# ProPrj_TC264_2025-12_27_1.net
KiCad netlist of a schematic drawn in EasyEDA Pro
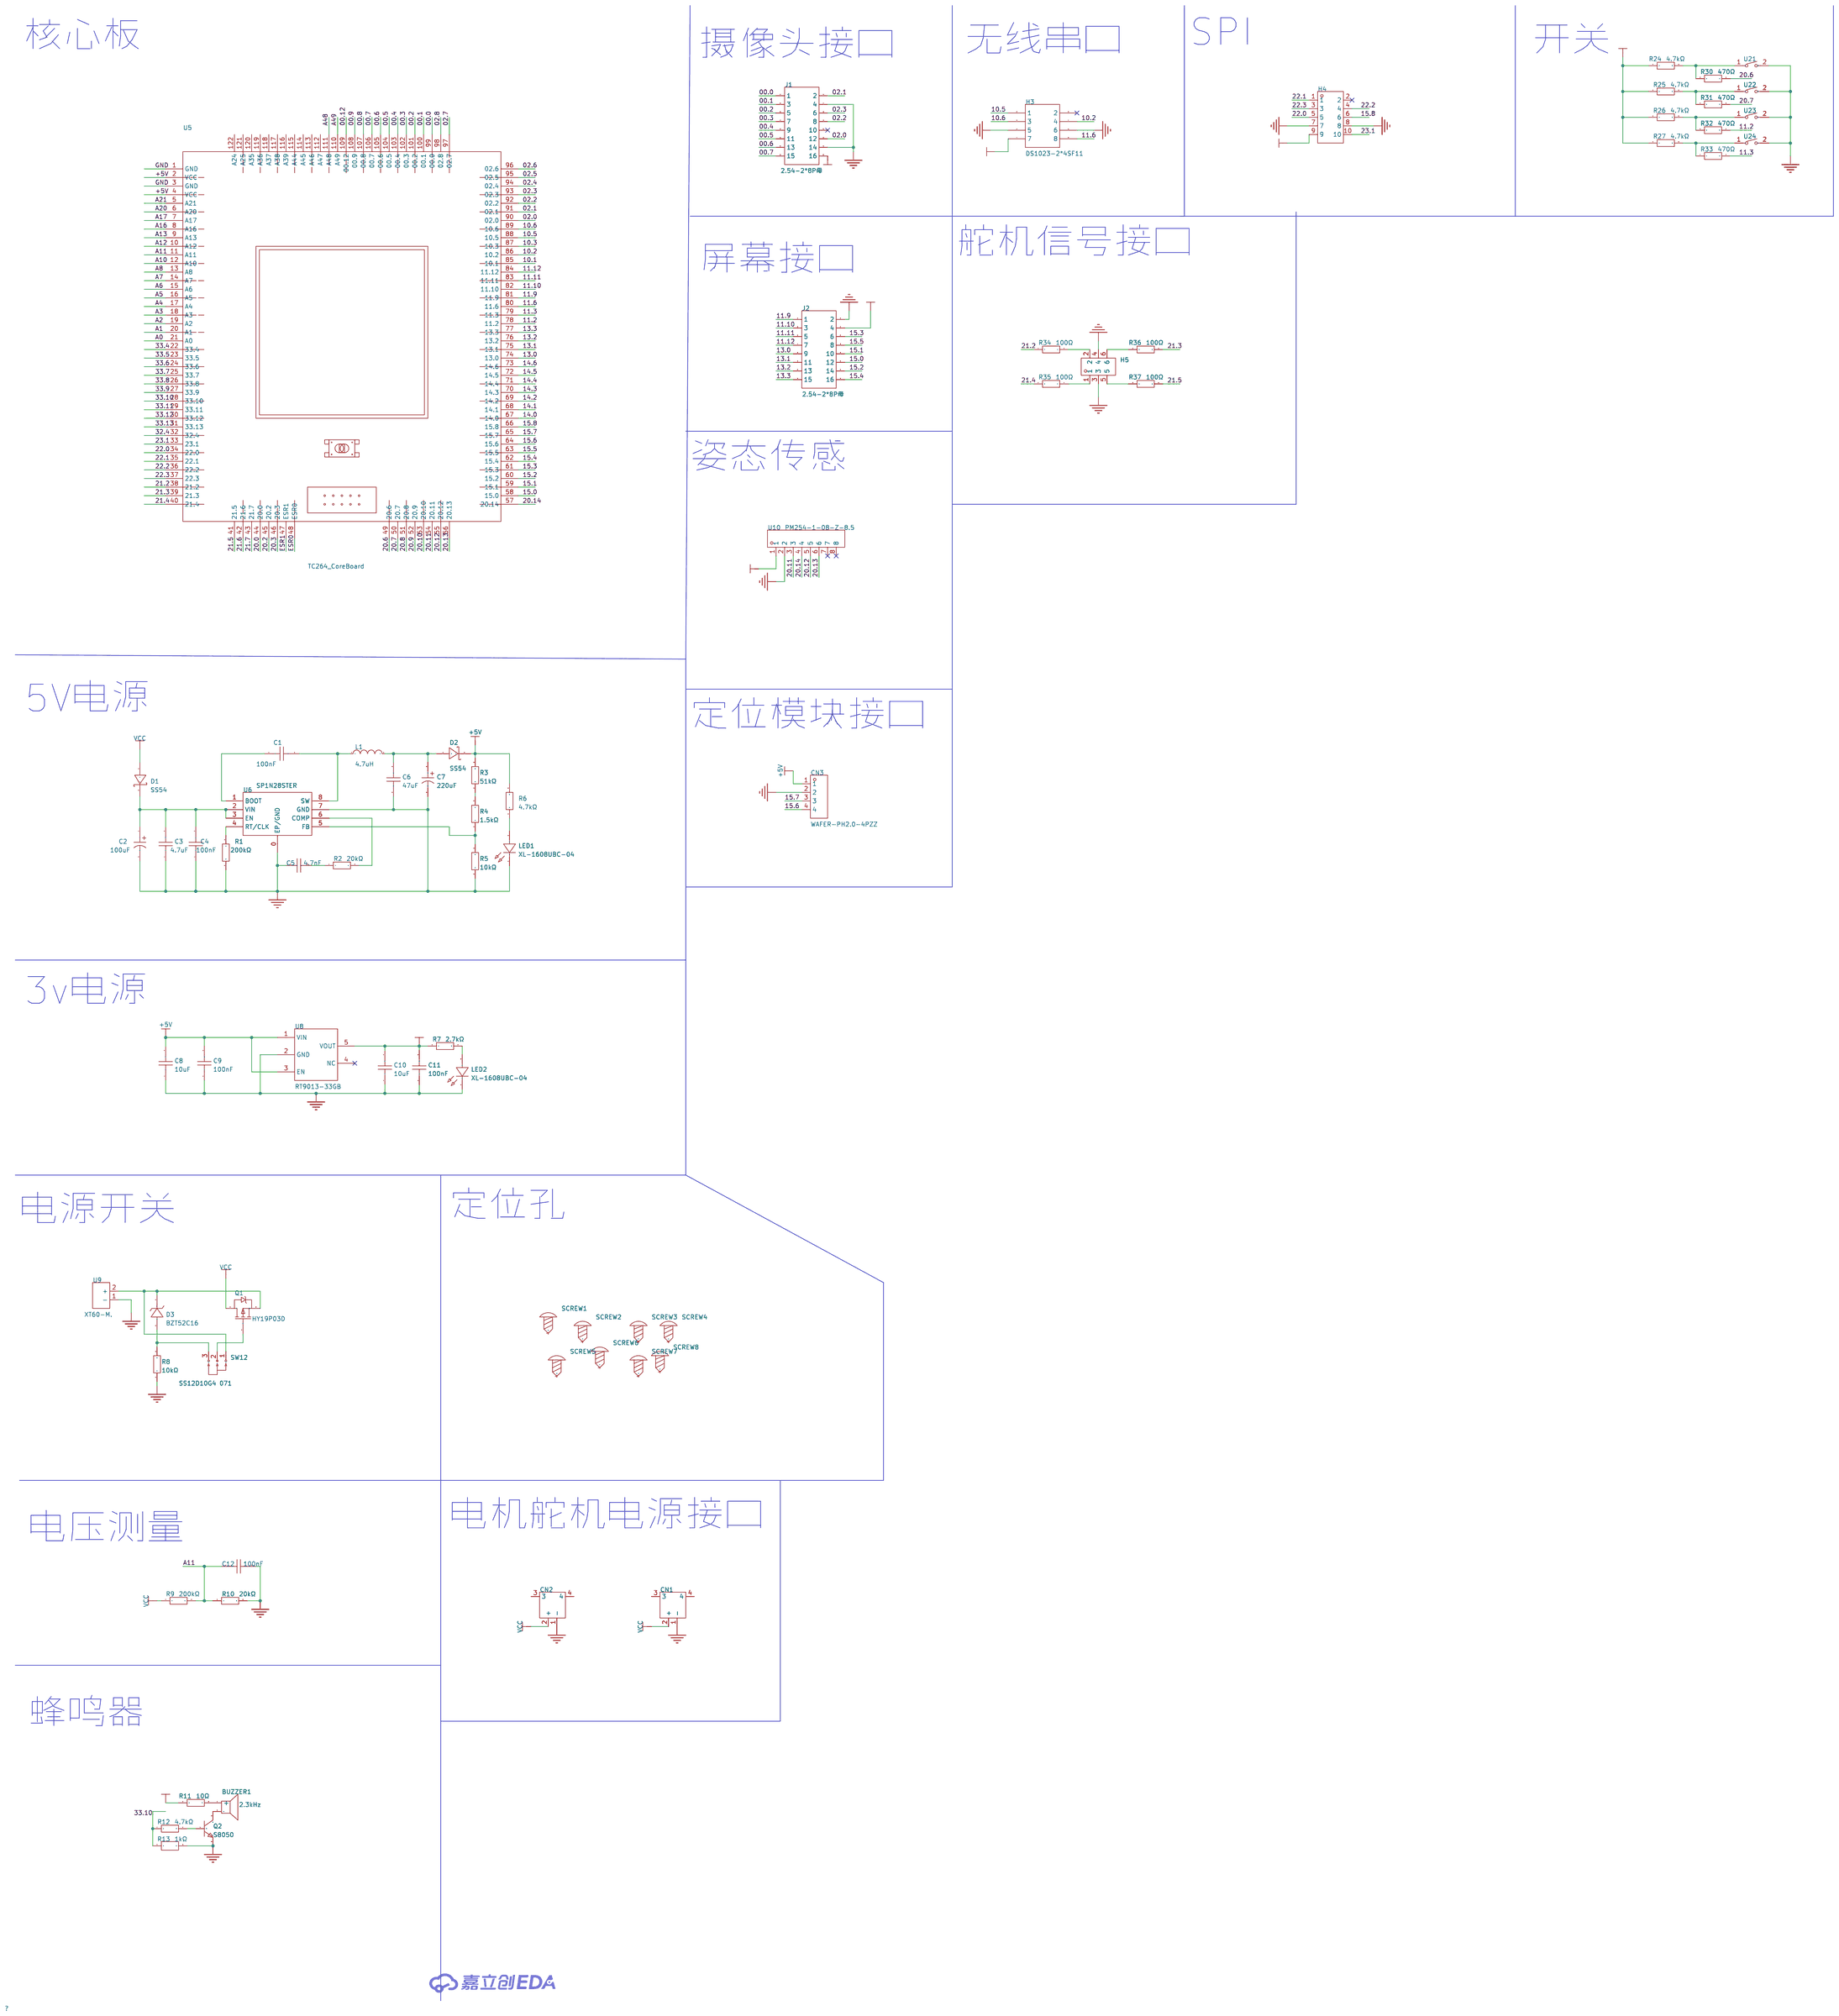
[diagram p0: schematic sheet]

(export (version "E")
  (design (tool "Eeschema 10.0.6"))
  (components
    (comp (ref "BUZZER1")
      (value "2.3kHz")
      (footprint "easyedapro:BUZ-TH_BD12.0-P7.60-D0.6-FD")
      (description "驱动方式:有源(内含驱动线路);构造类型:电磁式;频率:2.3kHz;声压(SPL):85dB;")
      (fields (field (name "Manufacturer Part") "TMB12A03") (field (name "Manufacturer") "华能"))
      (libsource (lib "easyedapro") (part "TMB12A03"))
    )
    (comp (ref "C1")
      (value "100nF")
      (footprint "easyedapro:C0603")
      (description "容值:100nF;精度:±10%;额定电压:50V;材质(温度系数):X7R;")
      (fields
        (field (name "Manufacturer Part") "CC0603KRX7R9BB104")
        (field (name "Manufacturer") "YAGEO(国巨)")
      )
      (libsource (lib "") (part "CC0603KRX7R9BB104_1"))
    )
    (comp (ref "C2")
      (value "100uF")
      (footprint "easyedapro:CAP-TH_BD6.3-P2.60-D0.6-FD-1")
      (description "容值:100uF;精度:±20%;额定电压:35V;纹波电流:2.6A@100kHz;等效串联电阻(ESR):28mΩ@100kHz;类型:聚合物;")
      (fields (field (name "Manufacturer Part") "JVJ25V100M6x5") (field (name "Manufacturer") "JIERR(捷而瑞)"))
      (libsource (lib "easyedapro") (part "PA35V100M6X8"))
    )
    (comp (ref "C3")
      (value "4.7uF")
      (footprint "easyedapro:C1206")
      (description "容值:4.7uF;精度:±10%;额定电压:35V;材质(温度系数):X5R;")
      (fields
        (field (name "Manufacturer Part") "CGA1206X5R475K350NT")
        (field (name "Manufacturer") "HRE(芯声)")
      )
      (libsource (lib "easyedapro") (part "CGA1206X5R475K350NT"))
    )
    (comp (ref "C4")
      (value "100nF")
      (footprint "easyedapro:C0603")
      (description "容值:100nF;精度:±10%;额定电压:50V;温度系数:X7R;")
      (fields
        (field (name "Manufacturer Part") "CC0603KRX7R9BB104")
        (field (name "Manufacturer") "YAGEO(国巨)")
      )
      (libsource (lib "easyedapro") (part "CC0603KRX7R9BB104"))
    )
    (comp (ref "C5")
      (value "4.7nF")
      (footprint "easyedapro:C0603")
      (description "容值:4.7nF;精度:±10%;额定电压:50V;温度系数:X7R;")
      (fields
        (field (name "Manufacturer Part") "CL10B472KB8NNNC")
        (field (name "Manufacturer") "SAMSUNG(三星)")
      )
      (libsource (lib "easyedapro") (part "CL10B472KB8NNNC"))
    )
    (comp (ref "C6")
      (value "47uF")
      (footprint "easyedapro:C1206")
      (description "容值:47uF;精度:±20%;额定电压:25V;温度系数:X5R;")
      (fields
        (field (name "Manufacturer Part") "HGC1206R5476M250NSPJ")
        (field (name "Manufacturer") "Chinocera(华瓷)")
      )
      (libsource (lib "easyedapro") (part "HGC1206R5476M250NSPJ"))
    )
    (comp (ref "C7")
      (value "220uF")
      (footprint "easyedapro:CAP-TH_BD10.0-P5.00-D0.6-FD_2")
      (description "容值:220uF;精度:±20%;额定电压:50V;纹波电流:3.5A@100kHz;等效串联电阻(ESR):20mΩ@100kHz;类型:聚合物;")
      (fields (field (name "Manufacturer Part") "RVT25V220M6X8") (field (name "Manufacturer") "JIERR(捷而瑞)"))
      (libsource (lib "easyedapro") (part "PA50V220M10X12"))
    )
    (comp (ref "C8")
      (value "10uF")
      (footprint "easyedapro:C0603")
      (description "容值:10uF;精度:±20%;额定电压:25V;温度系数:X5R;")
      (fields
        (field (name "Manufacturer Part") "CL10A106MA8NRNC")
        (field (name "Manufacturer") "SAMSUNG(三星)")
      )
      (libsource (lib "easyedapro") (part "CL10A106MA8NRNC"))
    )
    (comp (ref "C9")
      (value "100nF")
      (footprint "easyedapro:C0603")
      (description "容值:100nF;精度:±10%;额定电压:50V;温度系数:X7R;")
      (fields
        (field (name "Manufacturer Part") "CGA0603X7R104K500JT")
        (field (name "Manufacturer") "HRE(芯声)")
      )
      (libsource (lib "easyedapro") (part "CGA0603X7R104K500JT"))
    )
    (comp (ref "C10")
      (value "10uF")
      (footprint "easyedapro:C0603")
      (description "容值:10uF;精度:±20%;额定电压:25V;温度系数:X5R;")
      (fields
        (field (name "Manufacturer Part") "CL10A106MA8NRNC")
        (field (name "Manufacturer") "SAMSUNG(三星)")
      )
      (libsource (lib "easyedapro") (part "CL10A106MA8NRNC"))
    )
    (comp (ref "C11")
      (value "100nF")
      (footprint "easyedapro:C0603")
      (description "容值:100nF;精度:±10%;额定电压:50V;温度系数:X7R;")
      (fields
        (field (name "Manufacturer Part") "CGA0603X7R104K500JT")
        (field (name "Manufacturer") "HRE(芯声)")
      )
      (libsource (lib "easyedapro") (part "CGA0603X7R104K500JT"))
    )
    (comp (ref "C12")
      (value "100nF")
      (footprint "easyedapro:C0603")
      (description "容值:100nF;精度:±10%;额定电压:50V;温度系数:X7R;")
      (fields
        (field (name "Manufacturer Part") "FCC0603B104K500CT")
        (field (name "Manufacturer") "FOJAN(富捷)")
      )
      (libsource (lib "easyedapro") (part "FCC0603B104K500CT"))
    )
    (comp (ref "CN1")
      (value "XT30PW-M30.G.Y")
      (footprint "easyedapro:CONN-TH_XT30PW-M")
      (description "类别:-;类型1:-;")
      (fields (field (name "Manufacturer") "AMASS(艾迈斯)"))
      (libsource (lib "easyedapro") (part "XT30PW-M"))
    )
    (comp (ref "CN2")
      (value "XT30PW-M30.G.Y")
      (footprint "easyedapro:CONN-TH_XT30PW-M")
      (description "类别:-;类型1:-;")
      (fields (field (name "Manufacturer") "AMASS(艾迈斯)"))
      (libsource (lib "easyedapro") (part "XT30PW-M"))
    )
    (comp (ref "CN3")
      (value "WAFER-PH2.0-4PZZ")
      (footprint "easyedapro:CONN-TH_4P-P2.00_FWF20001-S04S22W5B")
      (fields (field (name "Manufacturer") "XUNPU(讯普)"))
      (libsource (lib "easyedapro") (part "WAFER-PH2.0-4PZZ"))
    )
    (comp (ref "D1")
      (value "SS54")
      (footprint "easyedapro:footprint_93fc")
      (fields (field (name "Manufacturer") "MDD"))
      (libsource (lib "easyedapro") (part "SS54"))
    )
    (comp (ref "D2")
      (value "SS54")
      (footprint "easyedapro:SMA_L4.4-W2.8-LS5.4-R-RD")
      (description "二极管配置:独立式;正向压降(Vf):550mV@5A;直流反向耐压(Vr):40V;整流电流:5A;")
      (fields (field (name "Manufacturer") "MDD(辰达半导体)"))
      (libsource (lib "easyedapro") (part "SS54_C22452"))
    )
    (comp (ref "D3")
      (value "BZT52C16")
      (footprint "easyedapro:SOD-123_L2.7-W1.7-LS3.8-RD")
      (description "二极管配置:独立式;稳压值(标称值):16V;稳压值(范围):15.3V~17.1V;耗散功率(Pd):500mW;")
      (fields (field (name "Manufacturer") "TWGMC(迪嘉)"))
      (libsource (lib "easyedapro") (part "BZT52C16_C727007"))
    )
    (comp (ref "H3")
      (value "DS1023-2*4SF11")
      (footprint "easyedapro:HDR-TH_8P-P2.54-V-F-R2-C4-S2.54")
      (description "插孔结构:2x4P;间距:2.54mm;行距:2.54mm;安装方式:直插;排数:双排;总孔位数:8P;塑高:-;触头材质:-;触头镀层:-;")
      (fields (field (name "Manufacturer") "CONNFLY"))
      (libsource (lib "easyedapro") (part "DS1023-2*4SF11"))
    )
    (comp (ref "H4")
      (value "PM254V-12-10P-H85")
      (footprint "easyedapro:HDR-TH_10P-P2.54-V-F-R2-C5-S2.54")
      (description "插孔结构:2x5P;间距:2.54mm;行距:2.54mm;安装方式:直插;排数:双排;总孔位数:10P;塑高:-;触头材质:黄铜;触头镀层:-;")
      (fields (field (name "Manufacturer") "XFCN(兴飞)"))
      (libsource (lib "easyedapro") (part "PM254V-12-10P-H85"))
    )
    (comp (ref "H5")
      (value "PZ254V-12-6P")
      (footprint "easyedapro:HDR-TH_6P-P2.54-V-M-R2-C3-S2.54")
      (fields (field (name "Manufacturer") "XFCN(兴飞)"))
      (libsource (lib "easyedapro") (part "PZ254V-12-6P"))
    )
    (comp (ref "J1")
      (value "2.54-2*8P母")
      (footprint "easyedapro:HDR-TH_16P-P2.54-V-F-R2-C8-S2.54")
      (description "插孔结构:2x8P;间距:2.54mm;行距:2.54mm;安装方式:直插;排数:双排;总孔位数:16P;塑高:-;触头材质:黄铜;触头镀层:-;")
      (fields (field (name "Manufacturer") "BOOMELE(博穆精密)"))
      (libsource (lib "easyedapro") (part "Header-Female-2.54_2x8"))
    )
    (comp (ref "J2")
      (value "2.54-2*8P母")
      (footprint "easyedapro:HDR-TH_16P-P2.54-V-F-R2-C8-S2.54")
      (description "插孔结构:2x8P;间距:2.54mm;行距:2.54mm;安装方式:直插;排数:双排;总孔位数:16P;塑高:-;触头材质:黄铜;触头镀层:-;")
      (fields (field (name "Manufacturer") "BOOMELE(博穆精密)"))
      (libsource (lib "easyedapro") (part "Header-Female-2.54_2x8"))
    )
    (comp (ref "L1")
      (value "4.7uH")
      (footprint "easyedapro:IND-SMD_L5.4-W5.2_FXL0530")
      (description "电感值:4.7uH;精度:±20%;额定电流:4.5A;饱和电流(Isat):5A;类型:一体成型电感;")
      (fields (field (name "Manufacturer Part") "FXL0530-4R7-M") (field (name "Manufacturer") "cjiang(长江微电)"))
      (libsource (lib "easyedapro") (part "FXL0530-4R7-M"))
    )
    (comp (ref "LED1")
      (value "XL-1608UBC-04")
      (footprint "easyedapro:LED0603-RD_BLUE")
      (fields (field (name "Manufacturer") "XINGLIGHT(成兴光)"))
      (libsource (lib "easyedapro") (part "XL-1608UBC-04"))
    )
    (comp (ref "LED2")
      (value "XL-1608UBC-04")
      (footprint "easyedapro:LED0603-RD_BLUE")
      (fields (field (name "Manufacturer") "XINGLIGHT(成兴光)"))
      (libsource (lib "easyedapro") (part "XL-1608UBC-04"))
    )
    (comp (ref "Q1")
      (value "HY19P03D")
      (footprint "easyedapro:TO-252-2_L6.6-W6.1-P4.57-LS9.9-TL-CW")
      (fields (field (name "Manufacturer") "HUAYI(华羿微)"))
      (libsource (lib "easyedapro") (part "HY19P03D"))
    )
    (comp (ref "Q2")
      (value "S8050")
      (footprint "easyedapro:SOT-23-3_L3.0-W1.7-P0.95-LS2.9-BR")
      (description "晶体管类型:NPN;集电极电流(Ic):500mA;集射极击穿电压(Vceo):25V;耗散功率(Pd):300mW;直流电流增益(hFE):-;")
      (fields (field (name "Manufacturer") "MDD(辰达半导体)"))
      (libsource (lib "easyedapro") (part "S8050-J3Y"))
    )
    (comp (ref "R1")
      (value "200kΩ")
      (footprint "easyedapro:R0805")
      (description "电阻类型:厚膜电阻;阻值:200kΩ;精度:±1%;功率:125mW;最大工作电压:150V;温度系数:±100ppm/°C;")
      (fields
        (field (name "Manufacturer Part") "0805W8F2003T5E")
        (field (name "Manufacturer") "UNI-ROYAL(厚声)")
      )
      (libsource (lib "easyedapro") (part "0805W8F2003T5E"))
    )
    (comp (ref "R2")
      (value "20kΩ")
      (footprint "easyedapro:R0805")
      (description "电阻类型:厚膜电阻;阻值:20kΩ;精度:±1%;功率:125mW;最大工作电压:150V;温度系数:±100ppm/°C;")
      (fields
        (field (name "Manufacturer Part") "0805W8F2002T5E")
        (field (name "Manufacturer") "UNI-ROYAL(厚声)")
      )
      (libsource (lib "easyedapro") (part "0805W8F2002T5E"))
    )
    (comp (ref "R3")
      (value "51kΩ")
      (footprint "easyedapro:R0805")
      (description "电阻类型:厚膜电阻;阻值:51kΩ;精度:±1%;功率:125mW;工作电压:150V;温度系数:±100ppm/°C;")
      (fields
        (field (name "Manufacturer Part") "0805W8F5102T5E")
        (field (name "Manufacturer") "UNI-ROYAL(厚声)")
      )
      (libsource (lib "easyedapro") (part "0805W8F5102T5E"))
    )
    (comp (ref "R4")
      (value "1.5kΩ")
      (footprint "easyedapro:R0805")
      (description "电阻类型:厚膜电阻;阻值:1.5kΩ;精度:±1%;功率:125mW;最大工作电压:150V;温度系数:±100ppm/°C;")
      (fields
        (field (name "Manufacturer Part") "0805W8F1501T5E")
        (field (name "Manufacturer") "UNI-ROYAL(厚声)")
      )
      (libsource (lib "easyedapro") (part "0805W8F1501T5E"))
    )
    (comp (ref "R5")
      (value "10kΩ")
      (footprint "easyedapro:R0805")
      (description "电阻类型:厚膜电阻;阻值:10kΩ;精度:±5%;功率:125mW;工作电压:150V;温度系数:±100ppm/°C;")
      (fields
        (field (name "Manufacturer Part") "0805W8J0103T5E")
        (field (name "Manufacturer") "UNI-ROYAL(厚声)")
      )
      (libsource (lib "easyedapro") (part "0805W8J0103T5E"))
    )
    (comp (ref "R6")
      (value "4.7kΩ")
      (footprint "easyedapro:R0805")
      (description "电阻类型:厚膜电阻;阻值:4.7kΩ;精度:±1%;功率:125mW;最大工作电压:150V;温度系数:±100ppm/°C;")
      (fields
        (field (name "Manufacturer Part") "0805W8F4701T5E")
        (field (name "Manufacturer") "UNI-ROYAL(厚声)")
      )
      (libsource (lib "easyedapro") (part "0805W8F4701T5E"))
    )
    (comp (ref "R7")
      (value "2.7kΩ")
      (footprint "easyedapro:R0805")
      (description "电阻类型:厚膜电阻;阻值:2.7kΩ;精度:±1%;功率:125mW;工作电压:150V;温度系数:±100ppm/°C;")
      (fields
        (field (name "Manufacturer Part") "0805W8F2701T5E")
        (field (name "Manufacturer") "UNI-ROYAL(厚声)")
      )
      (libsource (lib "easyedapro") (part "0805W8F2701T5E"))
    )
    (comp (ref "R8")
      (value "10kΩ")
      (footprint "easyedapro:R0805")
      (description "电阻类型:厚膜电阻;阻值:10kΩ;精度:±1%;功率:125mW;工作电压:150V;温度系数:±100ppm/°C;")
      (fields
        (field (name "Manufacturer Part") "0805W8F1002T5E")
        (field (name "Manufacturer") "UNI-ROYAL(厚声)")
      )
      (libsource (lib "easyedapro") (part "0805W8F1002T5E"))
    )
    (comp (ref "R9")
      (value "200kΩ")
      (footprint "easyedapro:R0603")
      (description "电阻类型:厚膜电阻;阻值:200kΩ;精度:±1%;功率:100mW;最大工作电压:75V;温度系数:±100ppm/°C;")
      (fields
        (field (name "Manufacturer Part") "0603WAF2003T5E")
        (field (name "Manufacturer") "UNI-ROYAL(厚声)")
      )
      (libsource (lib "easyedapro") (part "0603WAF2003T5E"))
    )
    (comp (ref "R10")
      (value "20kΩ")
      (footprint "easyedapro:R0603")
      (description "电阻类型:厚膜电阻;阻值:20kΩ;精度:±1%;功率:100mW;工作电压:75V;温度系数:±100ppm/°C;")
      (fields
        (field (name "Manufacturer Part") "0603WAF2002T5E")
        (field (name "Manufacturer") "UNI-ROYAL(厚声)")
      )
      (libsource (lib "easyedapro") (part "0603WAF2002T5E"))
    )
    (comp (ref "R11")
      (value "10Ω")
      (footprint "easyedapro:R0603")
      (description "电阻类型:厚膜电阻;阻值:10Ω;精度:±1%;功率:100mW;工作电压:75V;温度系数:±400ppm/°C;")
      (fields
        (field (name "Manufacturer Part") "0603WAF100JT5E")
        (field (name "Manufacturer") "UNI-ROYAL(厚声)")
      )
      (libsource (lib "easyedapro") (part "0603WAF100JT5E"))
    )
    (comp (ref "R12")
      (value "4.7kΩ")
      (footprint "easyedapro:R0603")
      (description "电阻类型:厚膜电阻;阻值:4.7kΩ;精度:±1%;功率:100mW;工作电压:75V;温度系数:±100ppm/°C;")
      (fields
        (field (name "Manufacturer Part") "0603WAF4701T5E")
        (field (name "Manufacturer") "UNI-ROYAL(厚声)")
      )
      (libsource (lib "easyedapro") (part "0603WAF4701T5E"))
    )
    (comp (ref "R13")
      (value "1kΩ")
      (footprint "easyedapro:R0603")
      (description "电阻类型:厚膜电阻;阻值:1kΩ;精度:±1%;功率:100mW;工作电压:75V;温度系数:±100ppm/°C;")
      (fields (field (name "Manufacturer Part") "FRC0603F1001TS") (field (name "Manufacturer") "FOJAN(富捷)"))
      (libsource (lib "easyedapro") (part "FRC0603F1001TS"))
    )
    (comp (ref "R24")
      (value "4.7kΩ")
      (footprint "easyedapro:R0603")
      (description "电阻类型:厚膜电阻;阻值:4.7kΩ;精度:±1%;功率:100mW;工作电压:75V;温度系数:±100ppm/°C;")
      (fields
        (field (name "Manufacturer Part") "0603WAF4701T5E")
        (field (name "Manufacturer") "UNI-ROYAL(厚声)")
      )
      (libsource (lib "easyedapro") (part "0603WAF4701T5E"))
    )
    (comp (ref "R25")
      (value "4.7kΩ")
      (footprint "easyedapro:R0603")
      (description "电阻类型:厚膜电阻;阻值:4.7kΩ;精度:±1%;功率:100mW;工作电压:75V;温度系数:±100ppm/°C;")
      (fields
        (field (name "Manufacturer Part") "0603WAF4701T5E")
        (field (name "Manufacturer") "UNI-ROYAL(厚声)")
      )
      (libsource (lib "easyedapro") (part "0603WAF4701T5E"))
    )
    (comp (ref "R26")
      (value "4.7kΩ")
      (footprint "easyedapro:R0603")
      (description "电阻类型:厚膜电阻;阻值:4.7kΩ;精度:±1%;功率:100mW;工作电压:75V;温度系数:±100ppm/°C;")
      (fields
        (field (name "Manufacturer Part") "0603WAF4701T5E")
        (field (name "Manufacturer") "UNI-ROYAL(厚声)")
      )
      (libsource (lib "easyedapro") (part "0603WAF4701T5E"))
    )
    (comp (ref "R27")
      (value "4.7kΩ")
      (footprint "easyedapro:R0603")
      (description "电阻类型:厚膜电阻;阻值:4.7kΩ;精度:±1%;功率:100mW;工作电压:75V;温度系数:±100ppm/°C;")
      (fields
        (field (name "Manufacturer Part") "0603WAF4701T5E")
        (field (name "Manufacturer") "UNI-ROYAL(厚声)")
      )
      (libsource (lib "easyedapro") (part "0603WAF4701T5E"))
    )
    (comp (ref "R30")
      (value "470Ω")
      (footprint "easyedapro:R0603")
      (description "电阻类型:厚膜电阻;阻值:470Ω;精度:±1%;功率:100mW;工作电压:75V;温度系数:±100ppm/°C;")
      (fields
        (field (name "Manufacturer Part") "0603WAF4700T5E")
        (field (name "Manufacturer") "UNI-ROYAL(厚声)")
      )
      (libsource (lib "easyedapro") (part "0603WAF4700T5E"))
    )
    (comp (ref "R31")
      (value "470Ω")
      (footprint "easyedapro:R0603")
      (description "电阻类型:厚膜电阻;阻值:470Ω;精度:±1%;功率:100mW;工作电压:75V;温度系数:±100ppm/°C;")
      (fields
        (field (name "Manufacturer Part") "0603WAF4700T5E")
        (field (name "Manufacturer") "UNI-ROYAL(厚声)")
      )
      (libsource (lib "easyedapro") (part "0603WAF4700T5E"))
    )
    (comp (ref "R32")
      (value "470Ω")
      (footprint "easyedapro:R0603")
      (description "电阻类型:厚膜电阻;阻值:470Ω;精度:±1%;功率:100mW;工作电压:75V;温度系数:±100ppm/°C;")
      (fields
        (field (name "Manufacturer Part") "0603WAF4700T5E")
        (field (name "Manufacturer") "UNI-ROYAL(厚声)")
      )
      (libsource (lib "easyedapro") (part "0603WAF4700T5E"))
    )
    (comp (ref "R33")
      (value "470Ω")
      (footprint "easyedapro:R0603")
      (description "电阻类型:厚膜电阻;阻值:470Ω;精度:±1%;功率:100mW;工作电压:75V;温度系数:±100ppm/°C;")
      (fields
        (field (name "Manufacturer Part") "0603WAF4700T5E")
        (field (name "Manufacturer") "UNI-ROYAL(厚声)")
      )
      (libsource (lib "easyedapro") (part "0603WAF4700T5E"))
    )
    (comp (ref "R34")
      (value "100Ω")
      (footprint "easyedapro:R0603")
      (description "电阻类型:厚膜电阻;阻值:100Ω;精度:±1%;功率:100mW;最大工作电压:75V;温度系数:±200ppm/°C;")
      (fields
        (field (name "Manufacturer Part") "0603WAF1000T5E")
        (field (name "Manufacturer") "UNI-ROYAL(厚声)")
      )
      (libsource (lib "easyedapro") (part "0603WAF1000T5E"))
    )
    (comp (ref "R35")
      (value "100Ω")
      (footprint "easyedapro:R0603")
      (description "电阻类型:厚膜电阻;阻值:100Ω;精度:±1%;功率:100mW;最大工作电压:75V;温度系数:±200ppm/°C;")
      (fields
        (field (name "Manufacturer Part") "0603WAF1000T5E")
        (field (name "Manufacturer") "UNI-ROYAL(厚声)")
      )
      (libsource (lib "easyedapro") (part "0603WAF1000T5E"))
    )
    (comp (ref "R36")
      (value "100Ω")
      (footprint "easyedapro:R0603")
      (description "电阻类型:厚膜电阻;阻值:100Ω;精度:±1%;功率:100mW;最大工作电压:75V;温度系数:±200ppm/°C;")
      (fields
        (field (name "Manufacturer Part") "0603WAF1000T5E")
        (field (name "Manufacturer") "UNI-ROYAL(厚声)")
      )
      (libsource (lib "easyedapro") (part "0603WAF1000T5E"))
    )
    (comp (ref "R37")
      (value "100Ω")
      (footprint "easyedapro:R0603")
      (description "电阻类型:厚膜电阻;阻值:100Ω;精度:±1%;功率:100mW;最大工作电压:75V;温度系数:±200ppm/°C;")
      (fields
        (field (name "Manufacturer Part") "0603WAF1000T5E")
        (field (name "Manufacturer") "UNI-ROYAL(厚声)")
      )
      (libsource (lib "easyedapro") (part "0603WAF1000T5E"))
    )
    (comp (ref "SCREW1")
      (value "~")
      (footprint "easyedapro:M3螺丝")
      (libsource (lib "easyedapro") (part "螺丝孔"))
    )
    (comp (ref "SCREW2")
      (value "~")
      (footprint "easyedapro:M3螺丝")
      (libsource (lib "easyedapro") (part "螺丝孔"))
    )
    (comp (ref "SCREW3")
      (value "~")
      (footprint "easyedapro:M3螺丝")
      (libsource (lib "easyedapro") (part "螺丝孔"))
    )
    (comp (ref "SCREW4")
      (value "~")
      (footprint "easyedapro:M3螺丝")
      (libsource (lib "easyedapro") (part "螺丝孔"))
    )
    (comp (ref "SCREW5")
      (value "~")
      (footprint "easyedapro:M3螺丝")
      (libsource (lib "easyedapro") (part "螺丝孔"))
    )
    (comp (ref "SCREW6")
      (value "~")
      (footprint "easyedapro:M3螺丝")
      (libsource (lib "easyedapro") (part "螺丝孔"))
    )
    (comp (ref "SCREW7")
      (value "~")
      (footprint "easyedapro:M3螺丝")
      (libsource (lib "easyedapro") (part "螺丝孔"))
    )
    (comp (ref "SCREW8")
      (value "~")
      (footprint "easyedapro:M3螺丝")
      (libsource (lib "easyedapro") (part "螺丝孔"))
    )
    (comp (ref "SW12")
      (value "SS12D10G4 071")
      (footprint "easyedapro:SW-TH_SHOU-HAN_SS12D10G4")
      (description "电路结构:单刀双掷;安装方式:立插;开关颜色:-;额定电流(DC):2A;额定电压(DC):125V;额定电流(AC):-;额定电压(AC):-;机械寿命:3千次;")
      (fields (field (name "Manufacturer") "SHOU HAN(首韩)"))
      (libsource (lib "easyedapro") (part "SS12D10G4 071"))
    )
    (comp (ref "U5")
      (value "TC264_CoreBoard")
      (footprint "easyedapro:TC264_main")
      (libsource (lib "easyedapro") (part "TC264"))
    )
    (comp (ref "U6")
      (value "SP1N28STER")
      (footprint "easyedapro:SOP-8E")
      (libsource (lib "easyedapro") (part "SP1N28STER"))
    )
    (comp (ref "U8")
      (value "RT9013-33GB")
      (footprint "easyedapro:SOT-23-5_L3.0-W1.7-P0.95-LS2.8-BL")
      (description "输出类型:固定;工作电压:5.5V;输出电压:3.3V;输出电流:500mA;电源纹波抑制比(PSRR):50dB@(10kHz);输出极性:正极;")
      (fields (field (name "Manufacturer") "RICHTEK(立锜)"))
      (libsource (lib "easyedapro") (part "RT9013-33GB"))
    )
    (comp (ref "U9")
      (value "XT60-M.")
      (footprint "easyedapro:CONN-TH_XT60")
      (description "类别:-;类型1:-;")
      (fields (field (name "Manufacturer") "AMASS(艾迈斯)"))
      (libsource (lib "easyedapro") (part "XT60"))
    )
    (comp (ref "U10")
      (value "PM254-1-08-Z-8.5")
      (footprint "easyedapro:HDR-TH_8P-P2.54-V-F")
      (fields (field (name "Manufacturer") "HCTL(华灿天禄)"))
      (libsource (lib "easyedapro") (part "PM254-1-08-Z-8.5"))
    )
    (comp (ref "U21")
      (value "GT-TC060A-H025-L1")
      (footprint "easyedapro:SW-SMD_L6.1-W3.5-LS8.0")
      (fields (field (name "Manufacturer") "G-Switch(品赞)"))
      (libsource (lib "easyedapro") (part "GT-TC060A-H025-L1"))
    )
    (comp (ref "U22")
      (value "GT-TC060A-H025-L1")
      (footprint "easyedapro:SW-SMD_L6.1-W3.5-LS8.0")
      (fields (field (name "Manufacturer") "G-Switch(品赞)"))
      (libsource (lib "easyedapro") (part "GT-TC060A-H025-L1"))
    )
    (comp (ref "U23")
      (value "GT-TC060A-H025-L1")
      (footprint "easyedapro:SW-SMD_L6.1-W3.5-LS8.0")
      (fields (field (name "Manufacturer") "G-Switch(品赞)"))
      (libsource (lib "easyedapro") (part "GT-TC060A-H025-L1"))
    )
    (comp (ref "U24")
      (value "GT-TC060A-H025-L1")
      (footprint "easyedapro:SW-SMD_L6.1-W3.5-LS8.0")
      (fields (field (name "Manufacturer") "G-Switch(品赞)"))
      (libsource (lib "easyedapro") (part "GT-TC060A-H025-L1"))
    )
  )
  (nets
    (net (code "1") (name "+5V") (class "Default")
      (node (ref "C8") (pin "2") (pinfunction "2_2") (pintype "unspecified"))
      (node (ref "C9") (pin "2") (pinfunction "2_2") (pintype "unspecified"))
      (node (ref "CN3") (pin "1") (pinfunction "1_1") (pintype "unspecified"))
      (node (ref "D2") (pin "2") (pinfunction "K_2") (pintype "unspecified"))
      (node (ref "H3") (pin "7") (pinfunction "7_7") (pintype "input"))
      (node (ref "H4") (pin "9") (pinfunction "9_9") (pintype "unspecified"))
      (node (ref "R3") (pin "2") (pinfunction "2_2") (pintype "input"))
      (node (ref "R6") (pin "2") (pinfunction "2_2") (pintype "input"))
      (node (ref "U5") (pin "2") (pinfunction "VCC_2") (pintype "input"))
      (node (ref "U5") (pin "4") (pinfunction "VCC_4") (pintype "input"))
      (node (ref "U8") (pin "1") (pinfunction "VIN_1") (pintype "unspecified"))
      (node (ref "U8") (pin "3") (pinfunction "EN_3") (pintype "unspecified"))
    )
    (net (code "2") (name "/00.0") (class "Default")
      (node (ref "J1") (pin "1") (pinfunction "1_1") (pintype "input"))
      (node (ref "U5") (pin "99") (pinfunction "00.0_99") (pintype "input"))
    )
    (net (code "3") (name "/00.1") (class "Default")
      (node (ref "J1") (pin "3") (pinfunction "3_3") (pintype "input"))
      (node (ref "U5") (pin "100") (pinfunction "00.1_100") (pintype "input"))
    )
    (net (code "4") (name "/00.2") (class "Default")
      (node (ref "J1") (pin "5") (pinfunction "5_5") (pintype "input"))
      (node (ref "U5") (pin "101") (pinfunction "00.2_101") (pintype "input"))
    )
    (net (code "5") (name "/00.3") (class "Default")
      (node (ref "J1") (pin "7") (pinfunction "7_7") (pintype "input"))
      (node (ref "U5") (pin "102") (pinfunction "00.3_102") (pintype "input"))
    )
    (net (code "6") (name "/00.4") (class "Default")
      (node (ref "J1") (pin "9") (pinfunction "9_9") (pintype "input"))
      (node (ref "U5") (pin "103") (pinfunction "00.4_103") (pintype "input"))
    )
    (net (code "7") (name "/00.5") (class "Default")
      (node (ref "J1") (pin "11") (pinfunction "11_11") (pintype "input"))
      (node (ref "U5") (pin "104") (pinfunction "00.5_104") (pintype "input"))
    )
    (net (code "8") (name "/00.6") (class "Default")
      (node (ref "J1") (pin "13") (pinfunction "13_13") (pintype "input"))
      (node (ref "U5") (pin "105") (pinfunction "00.6_105") (pintype "input"))
    )
    (net (code "9") (name "/00.7") (class "Default")
      (node (ref "J1") (pin "15") (pinfunction "15_15") (pintype "input"))
      (node (ref "U5") (pin "106") (pinfunction "00.7_106") (pintype "input"))
    )
    (net (code "10") (name "/00.8") (class "Default")
      (node (ref "U5") (pin "107") (pinfunction "00.8_107") (pintype "input"))
    )
    (net (code "11") (name "/00.9") (class "Default")
      (node (ref "U5") (pin "108") (pinfunction "00.9_108") (pintype "input"))
    )
    (net (code "12") (name "/00.12") (class "Default")
      (node (ref "U5") (pin "109") (pinfunction "00.12_109") (pintype "input"))
    )
    (net (code "13") (name "/02.0") (class "Default")
      (node (ref "J1") (pin "12") (pinfunction "12_12") (pintype "input"))
      (node (ref "U5") (pin "90") (pinfunction "02.0_90") (pintype "input"))
    )
    (net (code "14") (name "/02.1") (class "Default")
      (node (ref "J1") (pin "2") (pinfunction "2_2") (pintype "input"))
      (node (ref "U5") (pin "91") (pinfunction "02.1_91") (pintype "input"))
    )
    (net (code "15") (name "/02.2") (class "Default")
      (node (ref "J1") (pin "8") (pinfunction "8_8") (pintype "input"))
      (node (ref "U5") (pin "92") (pinfunction "02.2_92") (pintype "input"))
    )
    (net (code "16") (name "/02.3") (class "Default")
      (node (ref "J1") (pin "6") (pinfunction "6_6") (pintype "input"))
      (node (ref "U5") (pin "93") (pinfunction "02.3_93") (pintype "input"))
    )
    (net (code "17") (name "/02.4") (class "Default")
      (node (ref "U5") (pin "94") (pinfunction "02.4_94") (pintype "input"))
    )
    (net (code "18") (name "/02.5") (class "Default")
      (node (ref "U5") (pin "95") (pinfunction "02.5_95") (pintype "input"))
    )
    (net (code "19") (name "/02.6") (class "Default")
      (node (ref "U5") (pin "96") (pinfunction "02.6_96") (pintype "input"))
    )
    (net (code "20") (name "/02.7") (class "Default")
      (node (ref "U5") (pin "97") (pinfunction "02.7_97") (pintype "input"))
    )
    (net (code "21") (name "/02.8") (class "Default")
      (node (ref "U5") (pin "98") (pinfunction "02.8_98") (pintype "input"))
    )
    (net (code "22") (name "/10.1") (class "Default")
      (node (ref "U5") (pin "85") (pinfunction "10.1_85") (pintype "input"))
    )
    (net (code "23") (name "/10.2") (class "Default")
      (node (ref "H3") (pin "4") (pinfunction "4_4") (pintype "input"))
      (node (ref "U5") (pin "86") (pinfunction "10.2_86") (pintype "input"))
    )
    (net (code "24") (name "/10.3") (class "Default")
      (node (ref "U5") (pin "87") (pinfunction "10.3_87") (pintype "input"))
    )
    (net (code "25") (name "/10.5") (class "Default")
      (node (ref "H3") (pin "1") (pinfunction "1_1") (pintype "input"))
      (node (ref "U5") (pin "88") (pinfunction "10.5_88") (pintype "input"))
    )
    (net (code "26") (name "/10.6") (class "Default")
      (node (ref "H3") (pin "3") (pinfunction "3_3") (pintype "input"))
      (node (ref "U5") (pin "89") (pinfunction "10.6_89") (pintype "input"))
    )
    (net (code "27") (name "/11.2") (class "Default")
      (node (ref "R32") (pin "2") (pinfunction "2_2") (pintype "input"))
      (node (ref "U5") (pin "78") (pinfunction "11.2_78") (pintype "input"))
    )
    (net (code "28") (name "/11.3") (class "Default")
      (node (ref "R33") (pin "2") (pinfunction "2_2") (pintype "input"))
      (node (ref "U5") (pin "79") (pinfunction "11.3_79") (pintype "input"))
    )
    (net (code "29") (name "/11.6") (class "Default")
      (node (ref "H3") (pin "8") (pinfunction "8_8") (pintype "input"))
      (node (ref "U5") (pin "80") (pinfunction "11.6_80") (pintype "input"))
    )
    (net (code "30") (name "/11.9") (class "Default")
      (node (ref "J2") (pin "1") (pinfunction "1_1") (pintype "input"))
      (node (ref "U5") (pin "81") (pinfunction "11.9_81") (pintype "input"))
    )
    (net (code "31") (name "/11.10") (class "Default")
      (node (ref "J2") (pin "3") (pinfunction "3_3") (pintype "input"))
      (node (ref "U5") (pin "82") (pinfunction "11.10_82") (pintype "input"))
    )
    (net (code "32") (name "/11.11") (class "Default")
      (node (ref "J2") (pin "5") (pinfunction "5_5") (pintype "input"))
      (node (ref "U5") (pin "83") (pinfunction "11.11_83") (pintype "input"))
    )
    (net (code "33") (name "/11.12") (class "Default")
      (node (ref "J2") (pin "7") (pinfunction "7_7") (pintype "input"))
      (node (ref "U5") (pin "84") (pinfunction "11.12_84") (pintype "input"))
    )
    (net (code "34") (name "/13.0") (class "Default")
      (node (ref "J2") (pin "9") (pinfunction "9_9") (pintype "input"))
      (node (ref "U5") (pin "74") (pinfunction "13.0_74") (pintype "input"))
    )
    (net (code "35") (name "/13.1") (class "Default")
      (node (ref "J2") (pin "11") (pinfunction "11_11") (pintype "input"))
      (node (ref "U5") (pin "75") (pinfunction "13.1_75") (pintype "input"))
    )
    (net (code "36") (name "/13.2") (class "Default")
      (node (ref "J2") (pin "13") (pinfunction "13_13") (pintype "input"))
      (node (ref "U5") (pin "76") (pinfunction "13.2_76") (pintype "input"))
    )
    (net (code "37") (name "/13.3") (class "Default")
      (node (ref "J2") (pin "15") (pinfunction "15_15") (pintype "input"))
      (node (ref "U5") (pin "77") (pinfunction "13.3_77") (pintype "input"))
    )
    (net (code "38") (name "/14.0") (class "Default")
      (node (ref "U5") (pin "67") (pinfunction "14.0_67") (pintype "input"))
    )
    (net (code "39") (name "/14.1") (class "Default")
      (node (ref "U5") (pin "68") (pinfunction "14.1_68") (pintype "input"))
    )
    (net (code "40") (name "/14.2") (class "Default")
      (node (ref "U5") (pin "69") (pinfunction "14.2_69") (pintype "input"))
    )
    (net (code "41") (name "/14.3") (class "Default")
      (node (ref "U5") (pin "70") (pinfunction "14.3_70") (pintype "input"))
    )
    (net (code "42") (name "/14.4") (class "Default")
      (node (ref "U5") (pin "71") (pinfunction "14.4_71") (pintype "input"))
    )
    (net (code "43") (name "/14.5") (class "Default")
      (node (ref "U5") (pin "72") (pinfunction "14.5_72") (pintype "input"))
    )
    (net (code "44") (name "/14.6") (class "Default")
      (node (ref "U5") (pin "73") (pinfunction "14.6_73") (pintype "input"))
    )
    (net (code "45") (name "/15.0") (class "Default")
      (node (ref "J2") (pin "12") (pinfunction "12_12") (pintype "input"))
      (node (ref "U5") (pin "58") (pinfunction "15.0_58") (pintype "input"))
    )
    (net (code "46") (name "/15.1") (class "Default")
      (node (ref "J2") (pin "10") (pinfunction "10_10") (pintype "input"))
      (node (ref "U5") (pin "59") (pinfunction "15.1_59") (pintype "input"))
    )
    (net (code "47") (name "/15.2") (class "Default")
      (node (ref "J2") (pin "14") (pinfunction "14_14") (pintype "input"))
      (node (ref "U5") (pin "60") (pinfunction "15.2_60") (pintype "input"))
    )
    (net (code "48") (name "/15.3") (class "Default")
      (node (ref "J2") (pin "6") (pinfunction "6_6") (pintype "input"))
      (node (ref "U5") (pin "61") (pinfunction "15.3_61") (pintype "input"))
    )
    (net (code "49") (name "/15.4") (class "Default")
      (node (ref "J2") (pin "16") (pinfunction "16_16") (pintype "input"))
      (node (ref "U5") (pin "62") (pinfunction "15.4_62") (pintype "input"))
    )
    (net (code "50") (name "/15.5") (class "Default")
      (node (ref "J2") (pin "8") (pinfunction "8_8") (pintype "input"))
      (node (ref "U5") (pin "63") (pinfunction "15.5_63") (pintype "input"))
    )
    (net (code "51") (name "/15.6") (class "Default")
      (node (ref "CN3") (pin "4") (pinfunction "4_4") (pintype "unspecified"))
      (node (ref "U5") (pin "64") (pinfunction "15.6_64") (pintype "input"))
    )
    (net (code "52") (name "/15.7") (class "Default")
      (node (ref "CN3") (pin "3") (pinfunction "3_3") (pintype "unspecified"))
      (node (ref "U5") (pin "65") (pinfunction "15.7_65") (pintype "input"))
    )
    (net (code "53") (name "/15.8") (class "Default")
      (node (ref "H4") (pin "6") (pinfunction "6_6") (pintype "unspecified"))
      (node (ref "U5") (pin "66") (pinfunction "15.8_66") (pintype "input"))
    )
    (net (code "54") (name "/20.0") (class "Default")
      (node (ref "U5") (pin "44") (pinfunction "20.0_44") (pintype "input"))
    )
    (net (code "55") (name "/20.2") (class "Default")
      (node (ref "U5") (pin "45") (pinfunction "20.2_45") (pintype "input"))
    )
    (net (code "56") (name "/20.3") (class "Default")
      (node (ref "U5") (pin "46") (pinfunction "20.3_46") (pintype "input"))
    )
    (net (code "57") (name "/20.6") (class "Default")
      (node (ref "R30") (pin "2") (pinfunction "2_2") (pintype "input"))
      (node (ref "U5") (pin "49") (pinfunction "20.6_49") (pintype "input"))
    )
    (net (code "58") (name "/20.7") (class "Default")
      (node (ref "R31") (pin "2") (pinfunction "2_2") (pintype "input"))
      (node (ref "U5") (pin "50") (pinfunction "20.7_50") (pintype "input"))
    )
    (net (code "59") (name "/20.8") (class "Default")
      (node (ref "U5") (pin "51") (pinfunction "20.8_51") (pintype "input"))
    )
    (net (code "60") (name "/20.9") (class "Default")
      (node (ref "U5") (pin "52") (pinfunction "20.9_52") (pintype "input"))
    )
    (net (code "61") (name "/20.10") (class "Default")
      (node (ref "U5") (pin "53") (pinfunction "20.10_53") (pintype "input"))
    )
    (net (code "62") (name "/20.11") (class "Default")
      (node (ref "U10") (pin "3") (pinfunction "3_3") (pintype "unspecified"))
      (node (ref "U5") (pin "54") (pinfunction "20.11_54") (pintype "input"))
    )
    (net (code "63") (name "/20.12") (class "Default")
      (node (ref "U10") (pin "5") (pinfunction "5_5") (pintype "unspecified"))
      (node (ref "U5") (pin "55") (pinfunction "20.12_55") (pintype "input"))
    )
    (net (code "64") (name "/20.13") (class "Default")
      (node (ref "U10") (pin "6") (pinfunction "6_6") (pintype "unspecified"))
      (node (ref "U5") (pin "56") (pinfunction "20.13_56") (pintype "input"))
    )
    (net (code "65") (name "/20.14") (class "Default")
      (node (ref "U10") (pin "4") (pinfunction "4_4") (pintype "unspecified"))
      (node (ref "U5") (pin "57") (pinfunction "20.14_57") (pintype "input"))
    )
    (net (code "66") (name "/21.2") (class "Default")
      (node (ref "R34") (pin "1") (pinfunction "1_1") (pintype "input"))
      (node (ref "U5") (pin "38") (pinfunction "21.2_38") (pintype "input"))
    )
    (net (code "67") (name "/21.3") (class "Default")
      (node (ref "R36") (pin "2") (pinfunction "2_2") (pintype "input"))
      (node (ref "U5") (pin "39") (pinfunction "21.3_39") (pintype "input"))
    )
    (net (code "68") (name "/21.4") (class "Default")
      (node (ref "R35") (pin "1") (pinfunction "1_1") (pintype "input"))
      (node (ref "U5") (pin "40") (pinfunction "21.4_40") (pintype "input"))
    )
    (net (code "69") (name "/21.5") (class "Default")
      (node (ref "R37") (pin "2") (pinfunction "2_2") (pintype "input"))
      (node (ref "U5") (pin "41") (pinfunction "21.5_41") (pintype "input"))
    )
    (net (code "70") (name "/21.6") (class "Default")
      (node (ref "U5") (pin "42") (pinfunction "21.6_42") (pintype "input"))
    )
    (net (code "71") (name "/21.7") (class "Default")
      (node (ref "U5") (pin "43") (pinfunction "21.7_43") (pintype "input"))
    )
    (net (code "72") (name "/22.0") (class "Default")
      (node (ref "H4") (pin "5") (pinfunction "5_5") (pintype "unspecified"))
      (node (ref "U5") (pin "34") (pinfunction "22.0_34") (pintype "input"))
    )
    (net (code "73") (name "/22.1") (class "Default")
      (node (ref "H4") (pin "1") (pinfunction "1_1") (pintype "unspecified"))
      (node (ref "U5") (pin "35") (pinfunction "22.1_35") (pintype "input"))
    )
    (net (code "74") (name "/22.2") (class "Default")
      (node (ref "H4") (pin "4") (pinfunction "4_4") (pintype "unspecified"))
      (node (ref "U5") (pin "36") (pinfunction "22.2_36") (pintype "input"))
    )
    (net (code "75") (name "/22.3") (class "Default")
      (node (ref "H4") (pin "3") (pinfunction "3_3") (pintype "unspecified"))
      (node (ref "U5") (pin "37") (pinfunction "22.3_37") (pintype "input"))
    )
    (net (code "76") (name "/23.1") (class "Default")
      (node (ref "H4") (pin "10") (pinfunction "10_10") (pintype "unspecified"))
      (node (ref "U5") (pin "33") (pinfunction "23.1_33") (pintype "input"))
    )
    (net (code "77") (name "/32.4") (class "Default")
      (node (ref "U5") (pin "32") (pinfunction "32.4_32") (pintype "input"))
    )
    (net (code "78") (name "/33.4") (class "Default")
      (node (ref "U5") (pin "22") (pinfunction "33.4_22") (pintype "input"))
    )
    (net (code "79") (name "/33.5") (class "Default")
      (node (ref "U5") (pin "23") (pinfunction "33.5_23") (pintype "input"))
    )
    (net (code "80") (name "/33.6") (class "Default")
      (node (ref "U5") (pin "24") (pinfunction "33.6_24") (pintype "input"))
    )
    (net (code "81") (name "/33.7") (class "Default")
      (node (ref "U5") (pin "25") (pinfunction "33.7_25") (pintype "input"))
    )
    (net (code "82") (name "/33.8") (class "Default")
      (node (ref "U5") (pin "26") (pinfunction "33.8_26") (pintype "input"))
    )
    (net (code "83") (name "/33.9") (class "Default")
      (node (ref "U5") (pin "27") (pinfunction "33.9_27") (pintype "input"))
    )
    (net (code "84") (name "/33.10") (class "Default")
      (node (ref "R12") (pin "1") (pinfunction "1_1") (pintype "input"))
      (node (ref "R13") (pin "1") (pinfunction "1_1") (pintype "unspecified"))
      (node (ref "U5") (pin "28") (pinfunction "33.10_28") (pintype "input"))
    )
    (net (code "85") (name "/33.11") (class "Default")
      (node (ref "U5") (pin "29") (pinfunction "33.11_29") (pintype "input"))
    )
    (net (code "86") (name "/33.12") (class "Default")
      (node (ref "U5") (pin "30") (pinfunction "33.12_30") (pintype "input"))
    )
    (net (code "87") (name "/33.13") (class "Default")
      (node (ref "U5") (pin "31") (pinfunction "33.13_31") (pintype "input"))
    )
    (net (code "88") (name "/A0") (class "Default")
      (node (ref "U5") (pin "21") (pinfunction "A0_21") (pintype "input"))
    )
    (net (code "89") (name "/A1") (class "Default")
      (node (ref "U5") (pin "20") (pinfunction "A1_20") (pintype "input"))
    )
    (net (code "90") (name "/A2") (class "Default")
      (node (ref "U5") (pin "19") (pinfunction "A2_19") (pintype "input"))
    )
    (net (code "91") (name "/A3") (class "Default")
      (node (ref "U5") (pin "18") (pinfunction "A3_18") (pintype "input"))
    )
    (net (code "92") (name "/A4") (class "Default")
      (node (ref "U5") (pin "17") (pinfunction "A4_17") (pintype "input"))
    )
    (net (code "93") (name "/A5") (class "Default")
      (node (ref "U5") (pin "16") (pinfunction "A5_16") (pintype "input"))
    )
    (net (code "94") (name "/A6") (class "Default")
      (node (ref "U5") (pin "15") (pinfunction "A6_15") (pintype "input"))
    )
    (net (code "95") (name "/A7") (class "Default")
      (node (ref "U5") (pin "14") (pinfunction "A7_14") (pintype "input"))
    )
    (net (code "96") (name "/A8") (class "Default")
      (node (ref "U5") (pin "13") (pinfunction "A8_13") (pintype "input"))
    )
    (net (code "97") (name "/A10") (class "Default")
      (node (ref "U5") (pin "12") (pinfunction "A10_12") (pintype "input"))
    )
    (net (code "98") (name "/A11") (class "Default")
      (node (ref "C12") (pin "1") (pinfunction "1_1") (pintype "unspecified"))
      (node (ref "R10") (pin "1") (pinfunction "1_1") (pintype "input"))
      (node (ref "R9") (pin "2") (pinfunction "2_2") (pintype "input"))
      (node (ref "U5") (pin "11") (pinfunction "A11_11") (pintype "input"))
    )
    (net (code "99") (name "/A12") (class "Default")
      (node (ref "U5") (pin "10") (pinfunction "A12_10") (pintype "input"))
    )
    (net (code "100") (name "/A13") (class "Default")
      (node (ref "U5") (pin "9") (pinfunction "A13_9") (pintype "input"))
    )
    (net (code "101") (name "/A16") (class "Default")
      (node (ref "U5") (pin "8") (pinfunction "A16_8") (pintype "input"))
    )
    (net (code "102") (name "/A17") (class "Default")
      (node (ref "U5") (pin "7") (pinfunction "A17_7") (pintype "input"))
    )
    (net (code "103") (name "/A20") (class "Default")
      (node (ref "U5") (pin "6") (pinfunction "A20_6") (pintype "input"))
    )
    (net (code "104") (name "/A21") (class "Default")
      (node (ref "U5") (pin "5") (pinfunction "A21_5") (pintype "input"))
    )
    (net (code "105") (name "/A48") (class "Default")
      (node (ref "U5") (pin "111") (pinfunction "A48_111") (pintype "input"))
    )
    (net (code "106") (name "/A49") (class "Default")
      (node (ref "U5") (pin "110") (pinfunction "A49_110") (pintype "input"))
    )
    (net (code "107") (name "/ESR0") (class "Default")
      (node (ref "U5") (pin "48") (pinfunction "ESR0_48") (pintype "input"))
    )
    (net (code "108") (name "/ESR1") (class "Default")
      (node (ref "U5") (pin "47") (pinfunction "ESR1_47") (pintype "input"))
    )
    (net (code "109") (name "3V") (class "Default")
      (node (ref "C10") (pin "2") (pinfunction "2_2") (pintype "unspecified"))
      (node (ref "C11") (pin "2") (pinfunction "2_2") (pintype "unspecified"))
      (node (ref "J1") (pin "16") (pinfunction "16_16") (pintype "input"))
      (node (ref "J2") (pin "4") (pinfunction "4_4") (pintype "input"))
      (node (ref "R11") (pin "1") (pinfunction "1_1") (pintype "input"))
      (node (ref "R24") (pin "1") (pinfunction "1_1") (pintype "input"))
      (node (ref "R25") (pin "1") (pinfunction "1_1") (pintype "input"))
      (node (ref "R26") (pin "1") (pinfunction "1_1") (pintype "input"))
      (node (ref "R27") (pin "1") (pinfunction "1_1") (pintype "input"))
      (node (ref "R7") (pin "1") (pinfunction "1_1") (pintype "input"))
      (node (ref "U10") (pin "1") (pinfunction "1_1") (pintype "unspecified"))
      (node (ref "U8") (pin "5") (pinfunction "VOUT_5") (pintype "unspecified"))
    )
    (net (code "110") (name "GND") (class "Default")
      (node (ref "C10") (pin "1") (pinfunction "1_1") (pintype "unspecified"))
      (node (ref "C11") (pin "1") (pinfunction "1_1") (pintype "unspecified"))
      (node (ref "C12") (pin "2") (pinfunction "2_2") (pintype "unspecified"))
      (node (ref "C2") (pin "2") (pinfunction "2_2") (pintype "input"))
      (node (ref "C3") (pin "1") (pinfunction "1_1") (pintype "unspecified"))
      (node (ref "C4") (pin "1") (pinfunction "1_1") (pintype "unspecified"))
      (node (ref "C5") (pin "1") (pinfunction "1_1") (pintype "input"))
      (node (ref "C6") (pin "1") (pinfunction "1_1") (pintype "unspecified"))
      (node (ref "C7") (pin "2") (pinfunction "2_2") (pintype "input"))
      (node (ref "C8") (pin "1") (pinfunction "1_1") (pintype "unspecified"))
      (node (ref "C9") (pin "1") (pinfunction "1_1") (pintype "unspecified"))
      (node (ref "CN1") (pin "1") (pinfunction "-_1") (pintype "unspecified"))
      (node (ref "CN2") (pin "1") (pinfunction "-_1") (pintype "unspecified"))
      (node (ref "CN3") (pin "2") (pinfunction "2_2") (pintype "unspecified"))
      (node (ref "H3") (pin "5") (pinfunction "5_5") (pintype "input"))
      (node (ref "H3") (pin "6") (pinfunction "6_6") (pintype "input"))
      (node (ref "H4") (pin "7") (pinfunction "7_7") (pintype "unspecified"))
      (node (ref "H4") (pin "8") (pinfunction "8_8") (pintype "unspecified"))
      (node (ref "H5") (pin "3") (pinfunction "3_3") (pintype "unspecified"))
      (node (ref "H5") (pin "4") (pinfunction "4_4") (pintype "unspecified"))
      (node (ref "J1") (pin "14") (pinfunction "14_14") (pintype "input"))
      (node (ref "J1") (pin "4") (pinfunction "4_4") (pintype "input"))
      (node (ref "J2") (pin "2") (pinfunction "2_2") (pintype "input"))
      (node (ref "LED1") (pin "1") (pinfunction "K_1") (pintype "unspecified"))
      (node (ref "LED2") (pin "1") (pinfunction "K_1") (pintype "unspecified"))
      (node (ref "Q2") (pin "2") (pinfunction "E_2") (pintype "unspecified"))
      (node (ref "R1") (pin "1") (pinfunction "1_1") (pintype "input"))
      (node (ref "R10") (pin "2") (pinfunction "2_2") (pintype "input"))
      (node (ref "R13") (pin "2") (pinfunction "2_2") (pintype "unspecified"))
      (node (ref "R5") (pin "1") (pinfunction "1_1") (pintype "input"))
      (node (ref "R8") (pin "1") (pinfunction "1_1") (pintype "input"))
      (node (ref "U10") (pin "2") (pinfunction "2_2") (pintype "unspecified"))
      (node (ref "U21") (pin "2") (pinfunction "2_2") (pintype "unspecified"))
      (node (ref "U22") (pin "2") (pinfunction "2_2") (pintype "unspecified"))
      (node (ref "U23") (pin "2") (pinfunction "2_2") (pintype "unspecified"))
      (node (ref "U24") (pin "2") (pinfunction "2_2") (pintype "unspecified"))
      (node (ref "U5") (pin "1") (pinfunction "GND_1") (pintype "input"))
      (node (ref "U5") (pin "3") (pinfunction "GND_3") (pintype "input"))
      (node (ref "U6") (pin "0") (pinfunction "EP/GND_0") (pintype "input"))
      (node (ref "U6") (pin "7") (pinfunction "GND_7") (pintype "input"))
      (node (ref "U8") (pin "2") (pinfunction "GND_2") (pintype "unspecified"))
      (node (ref "U9") (pin "1") (pinfunction "-_1") (pintype "unspecified"))
    )
    (net (code "111") (name "Net-(BUZZER1-+)") (class "Default")
      (node (ref "BUZZER1") (pin "1") (pinfunction "+_1") (pintype "unspecified"))
      (node (ref "R11") (pin "2") (pinfunction "2_2") (pintype "input"))
    )
    (net (code "112") (name "Net-(C5-Pad2)") (class "Default")
      (node (ref "C5") (pin "2") (pinfunction "2_2") (pintype "input"))
      (node (ref "R2") (pin "1") (pinfunction "1_1") (pintype "input"))
    )
    (net (code "113") (name "Net-(D1-K)") (class "Default")
      (node (ref "C2") (pin "1") (pinfunction "1_1") (pintype "input"))
      (node (ref "C3") (pin "2") (pinfunction "2_2") (pintype "unspecified"))
      (node (ref "C4") (pin "2") (pinfunction "2_2") (pintype "unspecified"))
      (node (ref "D1") (pin "2") (pinfunction "K_2") (pintype "unspecified"))
      (node (ref "U6") (pin "2") (pinfunction "VIN_2") (pintype "input"))
      (node (ref "U6") (pin "3") (pinfunction "EN_3") (pintype "input"))
    )
    (net (code "114") (name "Net-(D2-A)") (class "Default")
      (node (ref "C6") (pin "2") (pinfunction "2_2") (pintype "unspecified"))
      (node (ref "C7") (pin "1") (pinfunction "1_1") (pintype "input"))
      (node (ref "D2") (pin "1") (pinfunction "A_1") (pintype "unspecified"))
      (node (ref "L1") (pin "2") (pinfunction "2_2") (pintype "unspecified"))
    )
    (net (code "115") (name "Net-(D3-A)") (class "Default")
      (node (ref "D3") (pin "2") (pinfunction "A_2") (pintype "unspecified"))
      (node (ref "R8") (pin "2") (pinfunction "2_2") (pintype "input"))
      (node (ref "SW12") (pin "3") (pinfunction "3_3") (pintype "unspecified"))
    )
    (net (code "116") (name "Net-(D3-K)") (class "Default")
      (node (ref "D3") (pin "1") (pinfunction "K_1") (pintype "unspecified"))
      (node (ref "Q1") (pin "3") (pinfunction "S_3") (pintype "unspecified"))
      (node (ref "SW12") (pin "1") (pinfunction "1_1") (pintype "unspecified"))
      (node (ref "U9") (pin "2") (pinfunction "+_2") (pintype "unspecified"))
    )
    (net (code "117") (name "Net-(H5-Pad1)") (class "Default")
      (node (ref "H5") (pin "1") (pinfunction "1_1") (pintype "unspecified"))
      (node (ref "R35") (pin "2") (pinfunction "2_2") (pintype "input"))
    )
    (net (code "118") (name "Net-(H5-Pad2)") (class "Default")
      (node (ref "H5") (pin "2") (pinfunction "2_2") (pintype "unspecified"))
      (node (ref "R34") (pin "2") (pinfunction "2_2") (pintype "input"))
    )
    (net (code "119") (name "Net-(H5-Pad5)") (class "Default")
      (node (ref "H5") (pin "5") (pinfunction "5_5") (pintype "unspecified"))
      (node (ref "R37") (pin "1") (pinfunction "1_1") (pintype "input"))
    )
    (net (code "120") (name "Net-(H5-Pad6)") (class "Default")
      (node (ref "H5") (pin "6") (pinfunction "6_6") (pintype "unspecified"))
      (node (ref "R36") (pin "1") (pinfunction "1_1") (pintype "input"))
    )
    (net (code "121") (name "Net-(LED1-A)") (class "Default")
      (node (ref "LED1") (pin "2") (pinfunction "A_2") (pintype "unspecified"))
      (node (ref "R6") (pin "1") (pinfunction "1_1") (pintype "input"))
    )
    (net (code "122") (name "Net-(LED2-A)") (class "Default")
      (node (ref "LED2") (pin "2") (pinfunction "A_2") (pintype "unspecified"))
      (node (ref "R7") (pin "2") (pinfunction "2_2") (pintype "input"))
    )
    (net (code "123") (name "Net-(Q1-G)") (class "Default")
      (node (ref "Q1") (pin "1") (pinfunction "G_1") (pintype "unspecified"))
      (node (ref "SW12") (pin "2") (pinfunction "2_2") (pintype "unspecified"))
    )
    (net (code "124") (name "Net-(Q2-B)") (class "Default")
      (node (ref "Q2") (pin "1") (pinfunction "B_1") (pintype "unspecified"))
      (node (ref "R12") (pin "2") (pinfunction "2_2") (pintype "input"))
    )
    (net (code "125") (name "Net-(Q2-C)") (class "Default")
      (node (ref "BUZZER1") (pin "2") (pinfunction "2_2") (pintype "unspecified"))
      (node (ref "Q2") (pin "3") (pinfunction "C_3") (pintype "unspecified"))
    )
    (net (code "126") (name "Net-(R3-Pad1)") (class "Default")
      (node (ref "R3") (pin "1") (pinfunction "1_1") (pintype "input"))
      (node (ref "R4") (pin "2") (pinfunction "2_2") (pintype "input"))
    )
    (net (code "127") (name "Net-(R24-Pad2)") (class "Default")
      (node (ref "R24") (pin "2") (pinfunction "2_2") (pintype "input"))
      (node (ref "R30") (pin "1") (pinfunction "1_1") (pintype "input"))
      (node (ref "U21") (pin "1") (pinfunction "1_1") (pintype "unspecified"))
    )
    (net (code "128") (name "Net-(R25-Pad2)") (class "Default")
      (node (ref "R25") (pin "2") (pinfunction "2_2") (pintype "input"))
      (node (ref "R31") (pin "1") (pinfunction "1_1") (pintype "input"))
      (node (ref "U22") (pin "1") (pinfunction "1_1") (pintype "unspecified"))
    )
    (net (code "129") (name "Net-(R26-Pad2)") (class "Default")
      (node (ref "R26") (pin "2") (pinfunction "2_2") (pintype "input"))
      (node (ref "R32") (pin "1") (pinfunction "1_1") (pintype "input"))
      (node (ref "U23") (pin "1") (pinfunction "1_1") (pintype "unspecified"))
    )
    (net (code "130") (name "Net-(R27-Pad2)") (class "Default")
      (node (ref "R27") (pin "2") (pinfunction "2_2") (pintype "input"))
      (node (ref "R33") (pin "1") (pinfunction "1_1") (pintype "input"))
      (node (ref "U24") (pin "1") (pinfunction "1_1") (pintype "unspecified"))
    )
    (net (code "131") (name "Net-(U6-BOOT)") (class "Default")
      (node (ref "C1") (pin "1") (pinfunction "1_1") (pintype "input"))
      (node (ref "U6") (pin "1") (pinfunction "BOOT_1") (pintype "input"))
    )
    (net (code "132") (name "Net-(U6-COMP)") (class "Default")
      (node (ref "R2") (pin "2") (pinfunction "2_2") (pintype "input"))
      (node (ref "U6") (pin "6") (pinfunction "COMP_6") (pintype "input"))
    )
    (net (code "133") (name "Net-(U6-FB)") (class "Default")
      (node (ref "R4") (pin "1") (pinfunction "1_1") (pintype "input"))
      (node (ref "R5") (pin "2") (pinfunction "2_2") (pintype "input"))
      (node (ref "U6") (pin "5") (pinfunction "FB_5") (pintype "input"))
    )
    (net (code "134") (name "Net-(U6-RT{slash}CLK)") (class "Default")
      (node (ref "R1") (pin "2") (pinfunction "2_2") (pintype "input"))
      (node (ref "U6") (pin "4") (pinfunction "RT/CLK_4") (pintype "input"))
    )
    (net (code "135") (name "Net-(U6-SW)") (class "Default")
      (node (ref "C1") (pin "2") (pinfunction "2_2") (pintype "input"))
      (node (ref "L1") (pin "1") (pinfunction "1_1") (pintype "unspecified"))
      (node (ref "U6") (pin "8") (pinfunction "SW_8") (pintype "input"))
    )
    (net (code "136") (name "VCC") (class "Default")
      (node (ref "CN1") (pin "2") (pinfunction "+_2") (pintype "unspecified"))
      (node (ref "CN2") (pin "2") (pinfunction "+_2") (pintype "unspecified"))
      (node (ref "D1") (pin "1") (pinfunction "A_1") (pintype "unspecified"))
      (node (ref "Q1") (pin "2") (pinfunction "D_2") (pintype "unspecified"))
      (node (ref "R9") (pin "1") (pinfunction "1_1") (pintype "input"))
    )
    (net (code "137") (name "unconnected-(CN1-Pad3)") (class "Default")
      (node (ref "CN1") (pin "3") (pinfunction "3_3") (pintype "unspecified"))
    )
    (net (code "138") (name "unconnected-(CN1-Pad4)") (class "Default")
      (node (ref "CN1") (pin "4") (pinfunction "4_4") (pintype "unspecified"))
    )
    (net (code "139") (name "unconnected-(CN2-Pad3)") (class "Default")
      (node (ref "CN2") (pin "3") (pinfunction "3_3") (pintype "unspecified"))
    )
    (net (code "140") (name "unconnected-(CN2-Pad4)") (class "Default")
      (node (ref "CN2") (pin "4") (pinfunction "4_4") (pintype "unspecified"))
    )
    (net (code "141") (name "unconnected-(H3-Pad2)") (class "Default")
      (node (ref "H3") (pin "2") (pinfunction "2_2") (pintype "input+no_connect"))
    )
    (net (code "142") (name "unconnected-(H4-Pad2)") (class "Default")
      (node (ref "H4") (pin "2") (pinfunction "2_2") (pintype "unspecified+no_connect"))
    )
    (net (code "143") (name "unconnected-(J1-Pad10)") (class "Default")
      (node (ref "J1") (pin "10") (pinfunction "10_10") (pintype "input+no_connect"))
    )
    (net (code "144") (name "unconnected-(SCREW1-Pad1)") (class "Default")
      (node (ref "SCREW1") (pin "1") (pinfunction "1_1") (pintype "input"))
    )
    (net (code "145") (name "unconnected-(SCREW2-Pad1)") (class "Default")
      (node (ref "SCREW2") (pin "1") (pinfunction "1_1") (pintype "input"))
    )
    (net (code "146") (name "unconnected-(SCREW3-Pad1)") (class "Default")
      (node (ref "SCREW3") (pin "1") (pinfunction "1_1") (pintype "input"))
    )
    (net (code "147") (name "unconnected-(SCREW4-Pad1)") (class "Default")
      (node (ref "SCREW4") (pin "1") (pinfunction "1_1") (pintype "input"))
    )
    (net (code "148") (name "unconnected-(SCREW5-Pad1)") (class "Default")
      (node (ref "SCREW5") (pin "1") (pinfunction "1_1") (pintype "input"))
    )
    (net (code "149") (name "unconnected-(SCREW6-Pad1)") (class "Default")
      (node (ref "SCREW6") (pin "1") (pinfunction "1_1") (pintype "input"))
    )
    (net (code "150") (name "unconnected-(SCREW7-Pad1)") (class "Default")
      (node (ref "SCREW7") (pin "1") (pinfunction "1_1") (pintype "input"))
    )
    (net (code "151") (name "unconnected-(SCREW8-Pad1)") (class "Default")
      (node (ref "SCREW8") (pin "1") (pinfunction "1_1") (pintype "input"))
    )
    (net (code "152") (name "unconnected-(U5-A24-Pad122)") (class "Default")
      (node (ref "U5") (pin "122") (pinfunction "A24_122") (pintype "input"))
    )
    (net (code "153") (name "unconnected-(U5-A25-Pad121)") (class "Default")
      (node (ref "U5") (pin "121") (pinfunction "A25_121") (pintype "input"))
    )
    (net (code "154") (name "unconnected-(U5-A35-Pad120)") (class "Default")
      (node (ref "U5") (pin "120") (pinfunction "A35_120") (pintype "input"))
    )
    (net (code "155") (name "unconnected-(U5-A36-Pad119)") (class "Default")
      (node (ref "U5") (pin "119") (pinfunction "A36_119") (pintype "input"))
    )
    (net (code "156") (name "unconnected-(U5-A37-Pad118)") (class "Default")
      (node (ref "U5") (pin "118") (pinfunction "A37_118") (pintype "input"))
    )
    (net (code "157") (name "unconnected-(U5-A38-Pad117)") (class "Default")
      (node (ref "U5") (pin "117") (pinfunction "A38_117") (pintype "input"))
    )
    (net (code "158") (name "unconnected-(U5-A39-Pad116)") (class "Default")
      (node (ref "U5") (pin "116") (pinfunction "A39_116") (pintype "input"))
    )
    (net (code "159") (name "unconnected-(U5-A44-Pad115)") (class "Default")
      (node (ref "U5") (pin "115") (pinfunction "A44_115") (pintype "input"))
    )
    (net (code "160") (name "unconnected-(U5-A45-Pad114)") (class "Default")
      (node (ref "U5") (pin "114") (pinfunction "A45_114") (pintype "input"))
    )
    (net (code "161") (name "unconnected-(U5-A46-Pad113)") (class "Default")
      (node (ref "U5") (pin "113") (pinfunction "A46_113") (pintype "input"))
    )
    (net (code "162") (name "unconnected-(U5-A47-Pad112)") (class "Default")
      (node (ref "U5") (pin "112") (pinfunction "A47_112") (pintype "input"))
    )
    (net (code "163") (name "unconnected-(U8-NC-Pad4)") (class "Default")
      (node (ref "U8") (pin "4") (pinfunction "NC_4") (pintype "unspecified+no_connect"))
    )
    (net (code "164") (name "unconnected-(U10-Pad7)") (class "Default")
      (node (ref "U10") (pin "7") (pinfunction "7_7") (pintype "unspecified+no_connect"))
    )
    (net (code "165") (name "unconnected-(U10-Pad8)") (class "Default")
      (node (ref "U10") (pin "8") (pinfunction "8_8") (pintype "unspecified+no_connect"))
    )
  )
)
